# sheet1.net
KiCad netlist of a schematic drawn in Altium Designer
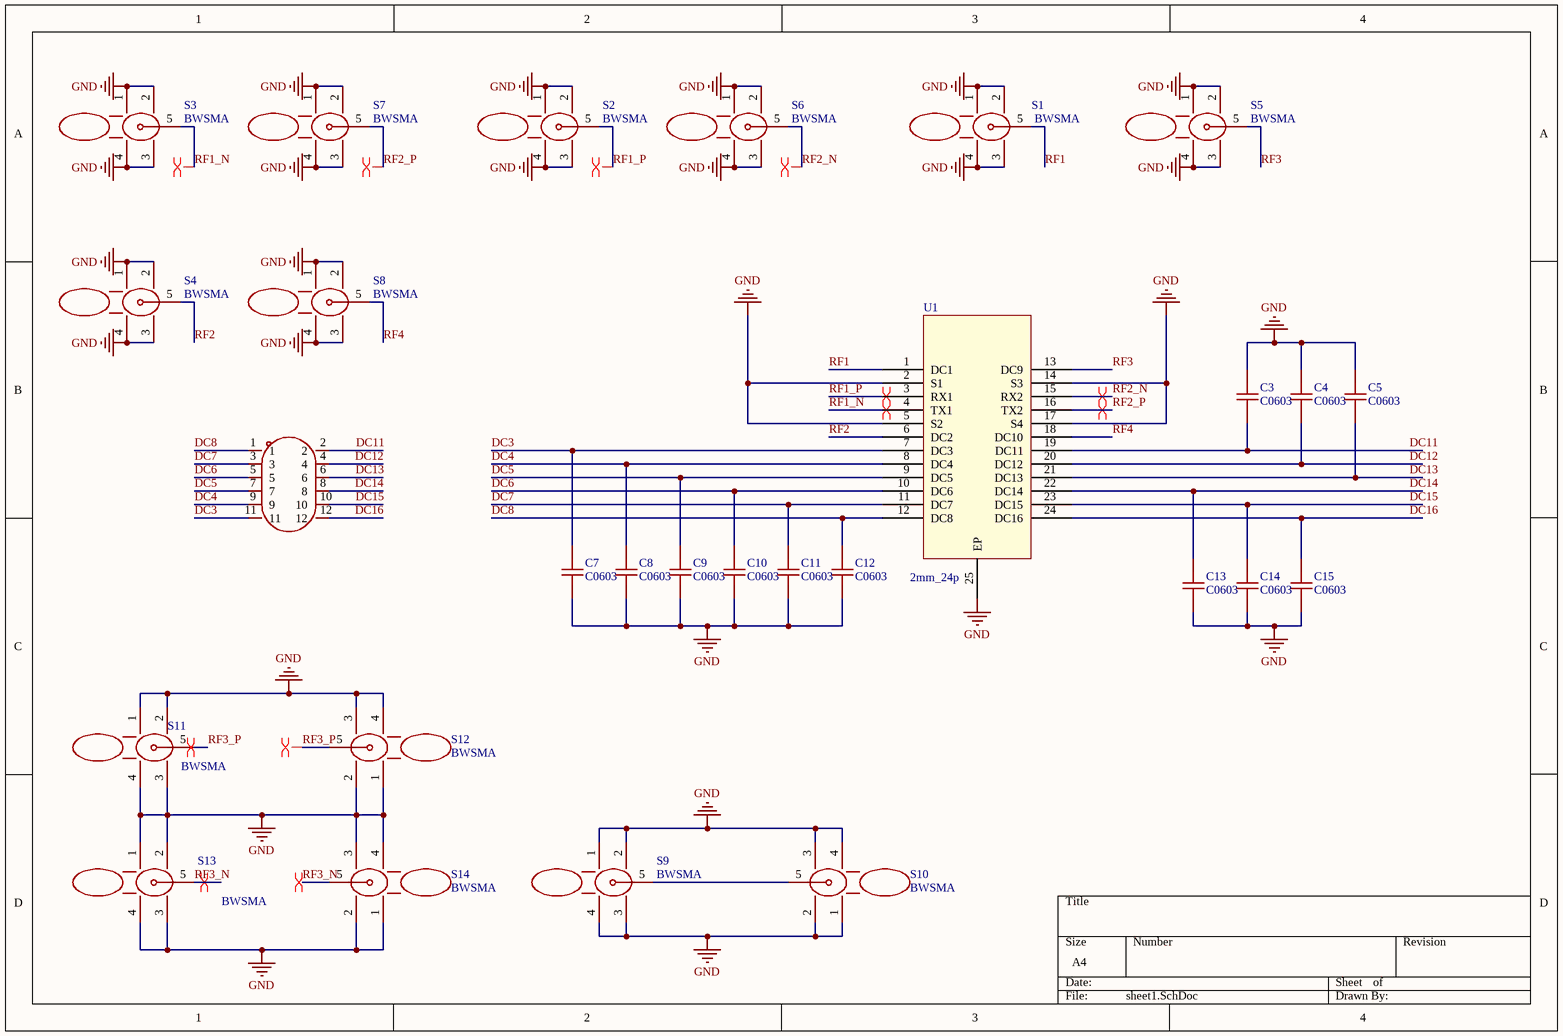
[diagram p0: sheet1.SchDoc]

(export (version "E")
  (design (tool "Eeschema 10.0.6"))
  (components
    (comp (ref "C3") (value "C0603") (footprint "C0603") (libsource (lib "Cap") (part "C0603")))
    (comp (ref "C4") (value "C0603") (footprint "C0603") (libsource (lib "Cap") (part "C0603")))
    (comp (ref "C5") (value "C0603") (footprint "C0603") (libsource (lib "Cap") (part "C0603")))
    (comp (ref "C7") (value "C0603") (footprint "C0603") (libsource (lib "Cap") (part "C0603")))
    (comp (ref "C8") (value "C0603") (footprint "C0603") (libsource (lib "Cap") (part "C0603")))
    (comp (ref "C9") (value "C0603") (footprint "C0603") (libsource (lib "Cap") (part "C0603")))
    (comp (ref "C10") (value "C0603") (footprint "C0603") (libsource (lib "Cap") (part "C0603")))
    (comp (ref "C11") (value "C0603") (footprint "C0603") (libsource (lib "Cap") (part "C0603")))
    (comp (ref "C12") (value "C0603") (footprint "C0603") (libsource (lib "Cap") (part "C0603")))
    (comp (ref "C13") (value "C0603") (footprint "C0603") (libsource (lib "Cap") (part "C0603")))
    (comp (ref "C14") (value "C0603") (footprint "C0603") (libsource (lib "Cap") (part "C0603")))
    (comp (ref "C15") (value "C0603") (footprint "C0603") (libsource (lib "Cap") (part "C0603")))
    (comp (ref "S1") (value "BWSMA") (footprint "BWSMA") (libsource (lib "SMA") (part "BWSMA")))
    (comp (ref "S2") (value "BWSMA") (footprint "BWSMA") (libsource (lib "SMA") (part "BWSMA")))
    (comp (ref "S3") (value "BWSMA") (footprint "BWSMA") (libsource (lib "SMA") (part "BWSMA")))
    (comp (ref "S4") (value "BWSMA") (footprint "BWSMA") (libsource (lib "SMA") (part "BWSMA")))
    (comp (ref "S5") (value "BWSMA") (footprint "BWSMA") (libsource (lib "SMA") (part "BWSMA")))
    (comp (ref "S6") (value "BWSMA") (footprint "BWSMA") (libsource (lib "SMA") (part "BWSMA")))
    (comp (ref "S7") (value "BWSMA") (footprint "BWSMA") (libsource (lib "SMA") (part "BWSMA")))
    (comp (ref "S8") (value "BWSMA") (footprint "BWSMA") (libsource (lib "SMA") (part "BWSMA")))
    (comp (ref "S9") (value "BWSMA") (footprint "BWSMA") (libsource (lib "SMA") (part "BWSMA")))
    (comp (ref "S10") (value "BWSMA") (footprint "BWSMA") (libsource (lib "SMA") (part "BWSMA")))
    (comp (ref "S11") (value "BWSMA") (footprint "BWSMA") (libsource (lib "SMA") (part "BWSMA")))
    (comp (ref "S12") (value "BWSMA") (footprint "BWSMA") (libsource (lib "SMA") (part "BWSMA")))
    (comp (ref "S13") (value "BWSMA") (footprint "BWSMA") (libsource (lib "SMA") (part "BWSMA")))
    (comp (ref "S14") (value "BWSMA") (footprint "BWSMA") (libsource (lib "SMA") (part "BWSMA")))
    (comp (ref "U1") (value "2mm_24p") (footprint "2MM_8AC_16DC") (libsource (lib "Chips") (part "2mm_24p")))
    (comp (ref "U2")
      (value "HX PZ2.54-2x6P ZZ")
      (footprint "2*6")
      (fields (field (name "MANUFACTURER") "hanxia(韩下)"))
      (libsource (lib "altium-import") (part "root_0_HX PZ2.54-2x6P ZZ_"))
    )
  )
  (nets
    (net (code "1") (name "/DC3") (class "Default")
      (node (ref "C7") (pin "2") (pinfunction "2_2") (pintype "passive"))
      (node (ref "U1") (pin "7") (pinfunction "DC3_7") (pintype "passive"))
      (node (ref "U2") (pin "11") (pinfunction "11_11") (pintype "passive"))
    )
    (net (code "2") (name "/DC4") (class "Default")
      (node (ref "C8") (pin "2") (pinfunction "2_2") (pintype "passive"))
      (node (ref "U1") (pin "8") (pinfunction "DC4_8") (pintype "passive"))
      (node (ref "U2") (pin "9") (pinfunction "9_9") (pintype "passive"))
    )
    (net (code "3") (name "/DC5") (class "Default")
      (node (ref "C9") (pin "2") (pinfunction "2_2") (pintype "passive"))
      (node (ref "U1") (pin "9") (pinfunction "DC5_9") (pintype "passive"))
      (node (ref "U2") (pin "7") (pinfunction "7_7") (pintype "passive"))
    )
    (net (code "4") (name "/DC6") (class "Default")
      (node (ref "C10") (pin "2") (pinfunction "2_2") (pintype "passive"))
      (node (ref "U1") (pin "10") (pinfunction "DC6_10") (pintype "passive"))
      (node (ref "U2") (pin "5") (pinfunction "5_5") (pintype "passive"))
    )
    (net (code "5") (name "/DC7") (class "Default")
      (node (ref "C11") (pin "2") (pinfunction "2_2") (pintype "passive"))
      (node (ref "U1") (pin "11") (pinfunction "DC7_11") (pintype "passive"))
      (node (ref "U2") (pin "3") (pinfunction "3_3") (pintype "passive"))
    )
    (net (code "6") (name "/DC8") (class "Default")
      (node (ref "C12") (pin "2") (pinfunction "2_2") (pintype "passive"))
      (node (ref "U1") (pin "12") (pinfunction "DC8_12") (pintype "passive"))
      (node (ref "U2") (pin "1") (pinfunction "1_1") (pintype "passive"))
    )
    (net (code "7") (name "/DC11") (class "Default")
      (node (ref "C3") (pin "1") (pinfunction "1_1") (pintype "passive"))
      (node (ref "U1") (pin "19") (pinfunction "DC11_19") (pintype "passive"))
      (node (ref "U2") (pin "2") (pinfunction "2_2") (pintype "passive"))
    )
    (net (code "8") (name "/DC12") (class "Default")
      (node (ref "C4") (pin "1") (pinfunction "1_1") (pintype "passive"))
      (node (ref "U1") (pin "20") (pinfunction "DC12_20") (pintype "passive"))
      (node (ref "U2") (pin "4") (pinfunction "4_4") (pintype "passive"))
    )
    (net (code "9") (name "/DC13") (class "Default")
      (node (ref "C5") (pin "1") (pinfunction "1_1") (pintype "passive"))
      (node (ref "U1") (pin "21") (pinfunction "DC13_21") (pintype "passive"))
      (node (ref "U2") (pin "6") (pinfunction "6_6") (pintype "passive"))
    )
    (net (code "10") (name "/DC14") (class "Default")
      (node (ref "C13") (pin "2") (pinfunction "2_2") (pintype "passive"))
      (node (ref "U1") (pin "22") (pinfunction "DC14_22") (pintype "passive"))
      (node (ref "U2") (pin "8") (pinfunction "8_8") (pintype "passive"))
    )
    (net (code "11") (name "/DC15") (class "Default")
      (node (ref "C14") (pin "2") (pinfunction "2_2") (pintype "passive"))
      (node (ref "U1") (pin "23") (pinfunction "DC15_23") (pintype "passive"))
      (node (ref "U2") (pin "10") (pinfunction "10_10") (pintype "passive"))
    )
    (net (code "12") (name "/DC16") (class "Default")
      (node (ref "C15") (pin "2") (pinfunction "2_2") (pintype "passive"))
      (node (ref "U1") (pin "24") (pinfunction "DC16_24") (pintype "passive"))
      (node (ref "U2") (pin "12") (pinfunction "12_12") (pintype "passive"))
    )
    (net (code "13") (name "/RF1") (class "Default")
      (node (ref "S1") (pin "5") (pinfunction "5_5") (pintype "passive"))
      (node (ref "U1") (pin "1") (pinfunction "DC1_1") (pintype "passive"))
    )
    (net (code "14") (name "/RF1_N") (class "Default")
      (node (ref "S3") (pin "5") (pinfunction "5_5") (pintype "passive"))
      (node (ref "U1") (pin "4") (pinfunction "TX1_4") (pintype "passive"))
    )
    (net (code "15") (name "/RF1_P") (class "Default")
      (node (ref "S2") (pin "5") (pinfunction "5_5") (pintype "passive"))
      (node (ref "U1") (pin "3") (pinfunction "RX1_3") (pintype "passive"))
    )
    (net (code "16") (name "/RF2") (class "Default")
      (node (ref "S4") (pin "5") (pinfunction "5_5") (pintype "passive"))
      (node (ref "U1") (pin "6") (pinfunction "DC2_6") (pintype "passive"))
    )
    (net (code "17") (name "/RF2_N") (class "Default")
      (node (ref "S6") (pin "5") (pinfunction "5_5") (pintype "passive"))
      (node (ref "U1") (pin "15") (pinfunction "RX2_15") (pintype "passive"))
    )
    (net (code "18") (name "/RF2_P") (class "Default")
      (node (ref "S7") (pin "5") (pinfunction "5_5") (pintype "passive"))
      (node (ref "U1") (pin "16") (pinfunction "TX2_16") (pintype "passive"))
    )
    (net (code "19") (name "/RF3") (class "Default")
      (node (ref "S5") (pin "5") (pinfunction "5_5") (pintype "passive"))
      (node (ref "U1") (pin "13") (pinfunction "DC9_13") (pintype "passive"))
    )
    (net (code "20") (name "/RF3_N") (class "Default")
      (node (ref "S13") (pin "5") (pinfunction "5_5") (pintype "passive"))
      (node (ref "S14") (pin "5") (pinfunction "5_5") (pintype "passive"))
    )
    (net (code "21") (name "/RF3_P") (class "Default")
      (node (ref "S11") (pin "5") (pinfunction "5_5") (pintype "passive"))
      (node (ref "S12") (pin "5") (pinfunction "5_5") (pintype "passive"))
    )
    (net (code "22") (name "/RF4") (class "Default")
      (node (ref "S8") (pin "5") (pinfunction "5_5") (pintype "passive"))
      (node (ref "U1") (pin "18") (pinfunction "DC10_18") (pintype "passive"))
    )
    (net (code "23") (name "GND") (class "Default")
      (node (ref "C10") (pin "1") (pinfunction "1_1") (pintype "passive"))
      (node (ref "C11") (pin "1") (pinfunction "1_1") (pintype "passive"))
      (node (ref "C12") (pin "1") (pinfunction "1_1") (pintype "passive"))
      (node (ref "C13") (pin "1") (pinfunction "1_1") (pintype "passive"))
      (node (ref "C14") (pin "1") (pinfunction "1_1") (pintype "passive"))
      (node (ref "C15") (pin "1") (pinfunction "1_1") (pintype "passive"))
      (node (ref "C3") (pin "2") (pinfunction "2_2") (pintype "passive"))
      (node (ref "C4") (pin "2") (pinfunction "2_2") (pintype "passive"))
      (node (ref "C5") (pin "2") (pinfunction "2_2") (pintype "passive"))
      (node (ref "C7") (pin "1") (pinfunction "1_1") (pintype "passive"))
      (node (ref "C8") (pin "1") (pinfunction "1_1") (pintype "passive"))
      (node (ref "C9") (pin "1") (pinfunction "1_1") (pintype "passive"))
      (node (ref "S1") (pin "1") (pinfunction "1_1") (pintype "passive"))
      (node (ref "S1") (pin "2") (pinfunction "2_2") (pintype "passive"))
      (node (ref "S1") (pin "3") (pinfunction "3_3") (pintype "passive"))
      (node (ref "S1") (pin "4") (pinfunction "4_4") (pintype "passive"))
      (node (ref "S10") (pin "1") (pinfunction "1_1") (pintype "passive"))
      (node (ref "S10") (pin "2") (pinfunction "2_2") (pintype "passive"))
      (node (ref "S10") (pin "3") (pinfunction "3_3") (pintype "passive"))
      (node (ref "S10") (pin "4") (pinfunction "4_4") (pintype "passive"))
      (node (ref "S11") (pin "1") (pinfunction "1_1") (pintype "passive"))
      (node (ref "S11") (pin "2") (pinfunction "2_2") (pintype "passive"))
      (node (ref "S11") (pin "3") (pinfunction "3_3") (pintype "passive"))
      (node (ref "S11") (pin "4") (pinfunction "4_4") (pintype "passive"))
      (node (ref "S12") (pin "1") (pinfunction "1_1") (pintype "passive"))
      (node (ref "S12") (pin "2") (pinfunction "2_2") (pintype "passive"))
      (node (ref "S12") (pin "3") (pinfunction "3_3") (pintype "passive"))
      (node (ref "S12") (pin "4") (pinfunction "4_4") (pintype "passive"))
      (node (ref "S13") (pin "1") (pinfunction "1_1") (pintype "passive"))
      (node (ref "S13") (pin "2") (pinfunction "2_2") (pintype "passive"))
      (node (ref "S13") (pin "3") (pinfunction "3_3") (pintype "passive"))
      (node (ref "S13") (pin "4") (pinfunction "4_4") (pintype "passive"))
      (node (ref "S14") (pin "1") (pinfunction "1_1") (pintype "passive"))
      (node (ref "S14") (pin "2") (pinfunction "2_2") (pintype "passive"))
      (node (ref "S14") (pin "3") (pinfunction "3_3") (pintype "passive"))
      (node (ref "S14") (pin "4") (pinfunction "4_4") (pintype "passive"))
      (node (ref "S2") (pin "1") (pinfunction "1_1") (pintype "passive"))
      (node (ref "S2") (pin "2") (pinfunction "2_2") (pintype "passive"))
      (node (ref "S2") (pin "3") (pinfunction "3_3") (pintype "passive"))
      (node (ref "S2") (pin "4") (pinfunction "4_4") (pintype "passive"))
      (node (ref "S3") (pin "1") (pinfunction "1_1") (pintype "passive"))
      (node (ref "S3") (pin "2") (pinfunction "2_2") (pintype "passive"))
      (node (ref "S3") (pin "3") (pinfunction "3_3") (pintype "passive"))
      (node (ref "S3") (pin "4") (pinfunction "4_4") (pintype "passive"))
      (node (ref "S4") (pin "1") (pinfunction "1_1") (pintype "passive"))
      (node (ref "S4") (pin "2") (pinfunction "2_2") (pintype "passive"))
      (node (ref "S4") (pin "3") (pinfunction "3_3") (pintype "passive"))
      (node (ref "S4") (pin "4") (pinfunction "4_4") (pintype "passive"))
      (node (ref "S5") (pin "1") (pinfunction "1_1") (pintype "passive"))
      (node (ref "S5") (pin "2") (pinfunction "2_2") (pintype "passive"))
      (node (ref "S5") (pin "3") (pinfunction "3_3") (pintype "passive"))
      (node (ref "S5") (pin "4") (pinfunction "4_4") (pintype "passive"))
      (node (ref "S6") (pin "1") (pinfunction "1_1") (pintype "passive"))
      (node (ref "S6") (pin "2") (pinfunction "2_2") (pintype "passive"))
      (node (ref "S6") (pin "3") (pinfunction "3_3") (pintype "passive"))
      (node (ref "S6") (pin "4") (pinfunction "4_4") (pintype "passive"))
      (node (ref "S7") (pin "1") (pinfunction "1_1") (pintype "passive"))
      (node (ref "S7") (pin "2") (pinfunction "2_2") (pintype "passive"))
      (node (ref "S7") (pin "3") (pinfunction "3_3") (pintype "passive"))
      (node (ref "S7") (pin "4") (pinfunction "4_4") (pintype "passive"))
      (node (ref "S8") (pin "1") (pinfunction "1_1") (pintype "passive"))
      (node (ref "S8") (pin "2") (pinfunction "2_2") (pintype "passive"))
      (node (ref "S8") (pin "3") (pinfunction "3_3") (pintype "passive"))
      (node (ref "S8") (pin "4") (pinfunction "4_4") (pintype "passive"))
      (node (ref "S9") (pin "1") (pinfunction "1_1") (pintype "passive"))
      (node (ref "S9") (pin "2") (pinfunction "2_2") (pintype "passive"))
      (node (ref "S9") (pin "3") (pinfunction "3_3") (pintype "passive"))
      (node (ref "S9") (pin "4") (pinfunction "4_4") (pintype "passive"))
      (node (ref "U1") (pin "14") (pinfunction "S3_14") (pintype "passive"))
      (node (ref "U1") (pin "17") (pinfunction "S4_17") (pintype "passive"))
      (node (ref "U1") (pin "2") (pinfunction "S1_2") (pintype "passive"))
      (node (ref "U1") (pin "25") (pinfunction "EP_25") (pintype "passive"))
      (node (ref "U1") (pin "5") (pinfunction "S2_5") (pintype "passive"))
    )
    (net (code "24") (name "Net-(S10-Pad5)") (class "Default")
      (node (ref "S10") (pin "5") (pinfunction "5_5") (pintype "passive"))
      (node (ref "S9") (pin "5") (pinfunction "5_5") (pintype "passive"))
    )
  )
)
